# 05_Sensor_Keypad.net
KiCad netlist of a schematic drawn in Altium Designer
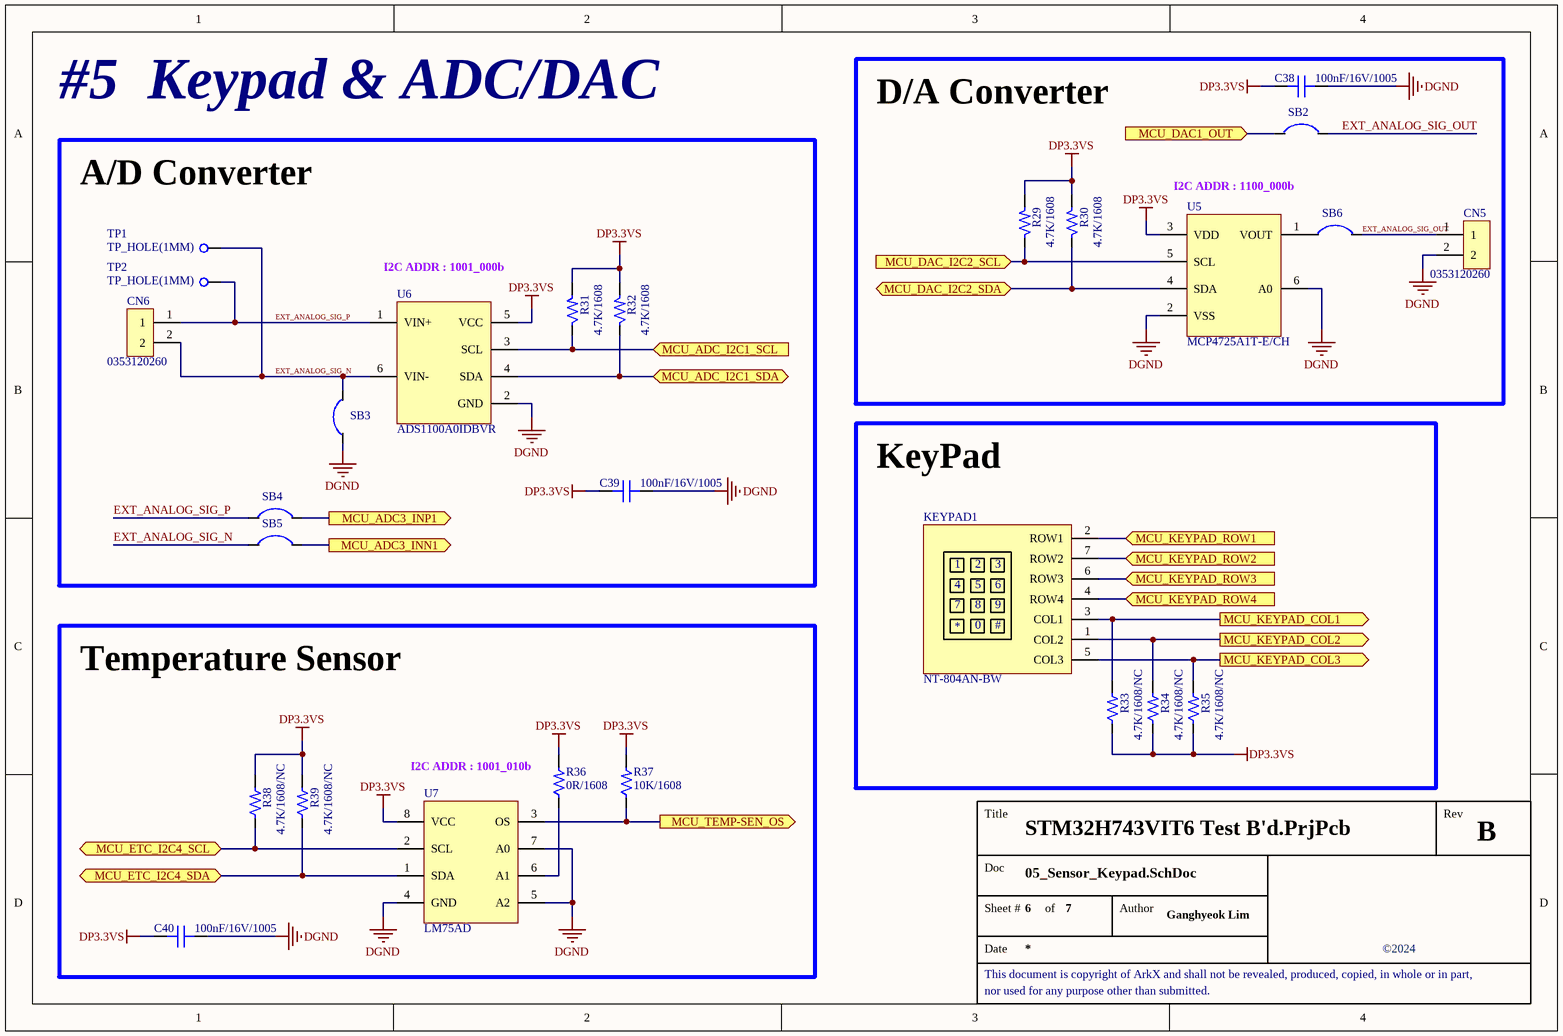
[diagram p0: 05_Sensor_Keypad.SchDoc]

(export (version "E")
  (design (tool "Eeschema 10.0.6"))
  (components
    (comp (ref "C38")
      (value "100nF/16V/1005")
      (footprint "CAP 1005 (0402_INCH)")
      (description "Ceramic CAP_100nF/16V/1005")
      (fields (field (name "LCSC PART #") "C1525"))
      (libsource (lib "Arkx") (part "CAP_100nF/16V/1005"))
    )
    (comp (ref "C39")
      (value "100nF/16V/1005")
      (footprint "CAP 1005 (0402_INCH)")
      (description "Ceramic CAP_100nF/16V/1005")
      (fields (field (name "LCSC PART #") "C1525"))
      (libsource (lib "Arkx") (part "CAP_100nF/16V/1005"))
    )
    (comp (ref "C40")
      (value "100nF/16V/1005")
      (footprint "CAP 1005 (0402_INCH)")
      (description "Ceramic CAP_100nF/16V/1005")
      (fields (field (name "LCSC PART #") "C1525"))
      (libsource (lib "Arkx") (part "CAP_100nF/16V/1005"))
    )
    (comp (ref "CN5")
      (value "0353120260")
      (footprint "CON 0353120260 (MOLEX)")
      (description "CONN HEADER VERT 2POS 2.5MM")
      (libsource (lib "") (part "CON_0353120260_1"))
    )
    (comp (ref "CN6")
      (value "0353120260")
      (footprint "CON 0353120260 (MOLEX)")
      (description "CONN HEADER VERT 2POS 2.5MM")
      (libsource (lib "Arkx") (part "CON_0353120260"))
    )
    (comp (ref "KEYPAD1")
      (value "NT-804AN-BW")
      (footprint "KEYPAD_NT-804AN-BW")
      (description "Legend(Character) type : Alpha-Numeric, Body/Key color : WHITE, Character color : BLACK")
      (libsource (lib "Arkx") (part "KEYPAD_NT-804AN-BW"))
    )
    (comp (ref "R29")
      (value "4.7K/1608")
      (footprint "RES 1608 (0603_inch)")
      (description "RES_4.7K/1608/0.1W")
      (fields (field (name "LCSC PART #") "C23162"))
      (libsource (lib "Arkx") (part "RES_4.7K/1608/0.1W"))
    )
    (comp (ref "R30")
      (value "4.7K/1608")
      (footprint "RES 1608 (0603_inch)")
      (description "RES_4.7K/1608/0.1W")
      (fields (field (name "LCSC PART #") "C23162"))
      (libsource (lib "Arkx") (part "RES_4.7K/1608/0.1W"))
    )
    (comp (ref "R31")
      (value "4.7K/1608")
      (footprint "RES 1608 (0603_inch)")
      (description "RES_4.7K/1608/0.1W")
      (fields (field (name "LCSC PART #") "C23162"))
      (libsource (lib "Arkx") (part "RES_4.7K/1608/0.1W"))
    )
    (comp (ref "R32")
      (value "4.7K/1608")
      (footprint "RES 1608 (0603_inch)")
      (description "RES_4.7K/1608/0.1W")
      (fields (field (name "LCSC PART #") "C23162"))
      (libsource (lib "Arkx") (part "RES_4.7K/1608/0.1W"))
    )
    (comp (ref "R33")
      (value "4.7K/1608/NC")
      (footprint "RES 1608 (0603_inch)/NC")
      (description "RES_4.7K/1608/0.1W")
      (libsource (lib "Arkx") (part "RES_NC_4.7K/1608/0.1W"))
    )
    (comp (ref "R34")
      (value "4.7K/1608/NC")
      (footprint "RES 1608 (0603_inch)/NC")
      (description "RES_4.7K/1608/0.1W")
      (libsource (lib "Arkx") (part "RES_NC_4.7K/1608/0.1W"))
    )
    (comp (ref "R35")
      (value "4.7K/1608/NC")
      (footprint "RES 1608 (0603_inch)/NC")
      (description "RES_4.7K/1608/0.1W")
      (libsource (lib "Arkx") (part "RES_NC_4.7K/1608/0.1W"))
    )
    (comp (ref "R36")
      (value "0R/1608")
      (footprint "RES 1608 (0603_inch)")
      (description "RES_0R/1608/0.1W")
      (fields (field (name "LCSC PART #") "C21189"))
      (libsource (lib "Arkx") (part "RES_0R/1608/0.1W"))
    )
    (comp (ref "R37")
      (value "10K/1608")
      (footprint "RES 1608 (0603_inch)")
      (description "RES_10K/1608/0.1W")
      (fields (field (name "LCSC PART #") "C25804"))
      (libsource (lib "Arkx") (part "RES_10K/1608/0.1W"))
    )
    (comp (ref "R38")
      (value "4.7K/1608/NC")
      (footprint "RES 1608 (0603_inch)/NC")
      (description "RES_4.7K/1608/0.1W")
      (libsource (lib "Arkx") (part "RES_NC_4.7K/1608/0.1W"))
    )
    (comp (ref "R39")
      (value "4.7K/1608/NC")
      (footprint "RES 1608 (0603_inch)/NC")
      (description "RES_4.7K/1608/0.1W")
      (libsource (lib "Arkx") (part "RES_NC_4.7K/1608/0.1W"))
    )
    (comp (ref "SB2")
      (value "SB")
      (footprint "SB (Solder-Bridge)")
      (description "SB_Solder-Bridge")
      (libsource (lib "Arkx") (part "SB_Solder-Bridge"))
    )
    (comp (ref "SB3")
      (value "SB")
      (footprint "SB (Solder-Bridge)")
      (description "SB_Solder-Bridge")
      (libsource (lib "") (part "SB_Solder-Bridge_1"))
    )
    (comp (ref "SB4")
      (value "SB")
      (footprint "SB (Solder-Bridge)")
      (description "SB_Solder-Bridge")
      (libsource (lib "Arkx") (part "SB_Solder-Bridge"))
    )
    (comp (ref "SB5")
      (value "SB")
      (footprint "SB (Solder-Bridge)")
      (description "SB_Solder-Bridge")
      (libsource (lib "Arkx") (part "SB_Solder-Bridge"))
    )
    (comp (ref "SB6")
      (value "SB")
      (footprint "SB (Solder-Bridge)")
      (description "SB_Solder-Bridge")
      (libsource (lib "Arkx") (part "SB_Solder-Bridge"))
    )
    (comp (ref "TP1")
      (value "TP_HOLE(1MM)")
      (footprint "TP_HOLE(1MM)")
      (libsource (lib "Arkx") (part "TP_HOLE(1MM)"))
    )
    (comp (ref "TP2")
      (value "TP_HOLE(1MM)")
      (footprint "TP_HOLE(1MM)")
      (libsource (lib "Arkx") (part "TP_HOLE(1MM)"))
    )
    (comp (ref "U5")
      (value "MCP4725A1T-E/CH")
      (footprint "SOT-23-6 (TI DBV PACKAGE)")
      (description "IC DAC 12BIT V-OUT SOT23-6")
      (fields (field (name "LCSC PART #") "C61423"))
      (libsource (lib "Arkx") (part "IC_DAC_MCP4725A1T-E/CH"))
    )
    (comp (ref "U6")
      (value "ADS1100A0IDBVR")
      (footprint "SOT-23-6 (TI DBV PACKAGE)")
      (description "IC ADC 16BIT SIGMA-DELTA SOT23-6")
      (fields (field (name "LCSC PART #") "C23361"))
      (libsource (lib "Arkx") (part "IC_ADC_ADS1100A0IDBVR"))
    )
    (comp (ref "U7")
      (value "LM75AD")
      (footprint "SOIC-8 150mil Wide (MICRO CHIP)")
      (description "Board Mount Temperature Sensors TEMP SENSOR DIGITAL")
      (fields (field (name "LCSC PART #") "C7963"))
      (libsource (lib "Arkx") (part "IC_TEMP-SEN_LM75AD"))
    )
  )
  (nets
    (net (code "1") (name "/EXT_ANALOG_SIG_N") (class "Default")
      (node (ref "CN6") (pin "2") (pinfunction "2_2") (pintype "passive"))
      (node (ref "SB3") (pin "2") (pinfunction "2_2") (pintype "passive"))
      (node (ref "SB5") (pin "1") (pinfunction "1_1") (pintype "passive"))
      (node (ref "TP1") (pin "1") (pinfunction "TP_1") (pintype "passive"))
      (node (ref "U6") (pin "6") (pinfunction "VIN-_6") (pintype "passive"))
    )
    (net (code "2") (name "/EXT_ANALOG_SIG_OUT") (class "Default")
      (node (ref "CN5") (pin "1") (pinfunction "1_1") (pintype "passive"))
      (node (ref "SB2") (pin "2") (pinfunction "2_2") (pintype "passive"))
      (node (ref "SB6") (pin "2") (pinfunction "2_2") (pintype "passive"))
    )
    (net (code "3") (name "/EXT_ANALOG_SIG_P") (class "Default")
      (node (ref "CN6") (pin "1") (pinfunction "1_1") (pintype "passive"))
      (node (ref "SB4") (pin "1") (pinfunction "1_1") (pintype "passive"))
      (node (ref "TP2") (pin "1") (pinfunction "TP_1") (pintype "passive"))
      (node (ref "U6") (pin "1") (pinfunction "VIN+_1") (pintype "passive"))
    )
    (net (code "4") (name "/MCU_ADC3_INN1") (class "Default")
      (node (ref "SB5") (pin "2") (pinfunction "2_2") (pintype "passive"))
    )
    (net (code "5") (name "/MCU_ADC3_INP1") (class "Default")
      (node (ref "SB4") (pin "2") (pinfunction "2_2") (pintype "passive"))
    )
    (net (code "6") (name "/MCU_ADC_I2C1_SCL") (class "Default")
      (node (ref "R31") (pin "1") (pinfunction "1_1") (pintype "passive"))
      (node (ref "U6") (pin "3") (pinfunction "SCL_3") (pintype "passive"))
    )
    (net (code "7") (name "/MCU_ADC_I2C1_SDA") (class "Default")
      (node (ref "R32") (pin "1") (pinfunction "1_1") (pintype "passive"))
      (node (ref "U6") (pin "4") (pinfunction "SDA_4") (pintype "passive"))
    )
    (net (code "8") (name "/MCU_DAC1_OUT") (class "Default")
      (node (ref "SB2") (pin "1") (pinfunction "1_1") (pintype "passive"))
    )
    (net (code "9") (name "/MCU_DAC_I2C2_SCL") (class "Default")
      (node (ref "R29") (pin "1") (pinfunction "1_1") (pintype "passive"))
      (node (ref "U5") (pin "5") (pinfunction "SCL_5") (pintype "passive"))
    )
    (net (code "10") (name "/MCU_DAC_I2C2_SDA") (class "Default")
      (node (ref "R30") (pin "1") (pinfunction "1_1") (pintype "passive"))
      (node (ref "U5") (pin "4") (pinfunction "SDA_4") (pintype "passive"))
    )
    (net (code "11") (name "/MCU_ETC_I2C4_SCL") (class "Default")
      (node (ref "R38") (pin "1") (pinfunction "1_1") (pintype "passive"))
      (node (ref "U7") (pin "2") (pinfunction "SCL_2") (pintype "passive"))
    )
    (net (code "12") (name "/MCU_ETC_I2C4_SDA") (class "Default")
      (node (ref "R39") (pin "1") (pinfunction "1_1") (pintype "passive"))
      (node (ref "U7") (pin "1") (pinfunction "SDA_1") (pintype "passive"))
    )
    (net (code "13") (name "/MCU_KEYPAD_COL1") (class "Default")
      (node (ref "KEYPAD1") (pin "3") (pinfunction "COL1_3") (pintype "passive"))
      (node (ref "R33") (pin "2") (pinfunction "2_2") (pintype "passive"))
    )
    (net (code "14") (name "/MCU_KEYPAD_COL2") (class "Default")
      (node (ref "KEYPAD1") (pin "1") (pinfunction "COL2_1") (pintype "passive"))
      (node (ref "R34") (pin "2") (pinfunction "2_2") (pintype "passive"))
    )
    (net (code "15") (name "/MCU_KEYPAD_COL3") (class "Default")
      (node (ref "KEYPAD1") (pin "5") (pinfunction "COL3_5") (pintype "passive"))
      (node (ref "R35") (pin "2") (pinfunction "2_2") (pintype "passive"))
    )
    (net (code "16") (name "/MCU_KEYPAD_ROW1") (class "Default")
      (node (ref "KEYPAD1") (pin "2") (pinfunction "ROW1_2") (pintype "passive"))
    )
    (net (code "17") (name "/MCU_KEYPAD_ROW2") (class "Default")
      (node (ref "KEYPAD1") (pin "7") (pinfunction "ROW2_7") (pintype "passive"))
    )
    (net (code "18") (name "/MCU_KEYPAD_ROW3") (class "Default")
      (node (ref "KEYPAD1") (pin "6") (pinfunction "ROW3_6") (pintype "passive"))
    )
    (net (code "19") (name "/MCU_KEYPAD_ROW4") (class "Default")
      (node (ref "KEYPAD1") (pin "4") (pinfunction "ROW4_4") (pintype "passive"))
    )
    (net (code "20") (name "/MCU_TEMP-SEN_OS") (class "Default")
      (node (ref "R37") (pin "1") (pinfunction "1_1") (pintype "passive"))
      (node (ref "U7") (pin "3") (pinfunction "OS_3") (pintype "passive"))
    )
    (net (code "21") (name "DGND") (class "Default")
      (node (ref "C38") (pin "1") (pinfunction "1_1") (pintype "passive"))
      (node (ref "C39") (pin "1") (pinfunction "1_1") (pintype "passive"))
      (node (ref "C40") (pin "1") (pinfunction "1_1") (pintype "passive"))
      (node (ref "CN5") (pin "2") (pinfunction "2_2") (pintype "passive"))
      (node (ref "SB3") (pin "1") (pinfunction "1_1") (pintype "passive"))
      (node (ref "U5") (pin "2") (pinfunction "VSS_2") (pintype "passive"))
      (node (ref "U5") (pin "6") (pinfunction "A0_6") (pintype "passive"))
      (node (ref "U6") (pin "2") (pinfunction "GND_2") (pintype "passive"))
      (node (ref "U7") (pin "4") (pinfunction "GND_4") (pintype "passive"))
      (node (ref "U7") (pin "5") (pinfunction "A2_5") (pintype "passive"))
      (node (ref "U7") (pin "7") (pinfunction "A0_7") (pintype "passive"))
    )
    (net (code "22") (name "DP3.3VS") (class "Default")
      (node (ref "C38") (pin "2") (pinfunction "2_2") (pintype "passive"))
      (node (ref "C39") (pin "2") (pinfunction "2_2") (pintype "passive"))
      (node (ref "C40") (pin "2") (pinfunction "2_2") (pintype "passive"))
      (node (ref "R29") (pin "2") (pinfunction "2_2") (pintype "passive"))
      (node (ref "R30") (pin "2") (pinfunction "2_2") (pintype "passive"))
      (node (ref "R31") (pin "2") (pinfunction "2_2") (pintype "passive"))
      (node (ref "R32") (pin "2") (pinfunction "2_2") (pintype "passive"))
      (node (ref "R33") (pin "1") (pinfunction "1_1") (pintype "passive"))
      (node (ref "R34") (pin "1") (pinfunction "1_1") (pintype "passive"))
      (node (ref "R35") (pin "1") (pinfunction "1_1") (pintype "passive"))
      (node (ref "R36") (pin "2") (pinfunction "2_2") (pintype "passive"))
      (node (ref "R37") (pin "2") (pinfunction "2_2") (pintype "passive"))
      (node (ref "R38") (pin "2") (pinfunction "2_2") (pintype "passive"))
      (node (ref "R39") (pin "2") (pinfunction "2_2") (pintype "passive"))
      (node (ref "U5") (pin "3") (pinfunction "VDD_3") (pintype "passive"))
      (node (ref "U6") (pin "5") (pinfunction "VCC_5") (pintype "passive"))
      (node (ref "U7") (pin "8") (pinfunction "VCC_8") (pintype "passive"))
    )
    (net (code "23") (name "Net-(U5-VOUT)") (class "Default")
      (node (ref "SB6") (pin "1") (pinfunction "1_1") (pintype "passive"))
      (node (ref "U5") (pin "1") (pinfunction "VOUT_1") (pintype "passive"))
    )
    (net (code "24") (name "Net-(U7-A1)") (class "Default")
      (node (ref "R36") (pin "1") (pinfunction "1_1") (pintype "passive"))
      (node (ref "U7") (pin "6") (pinfunction "A1_6") (pintype "passive"))
    )
  )
)
